# ST-Link-V2_2-Mini.net
KiCad netlist of a schematic drawn in Altium Designer
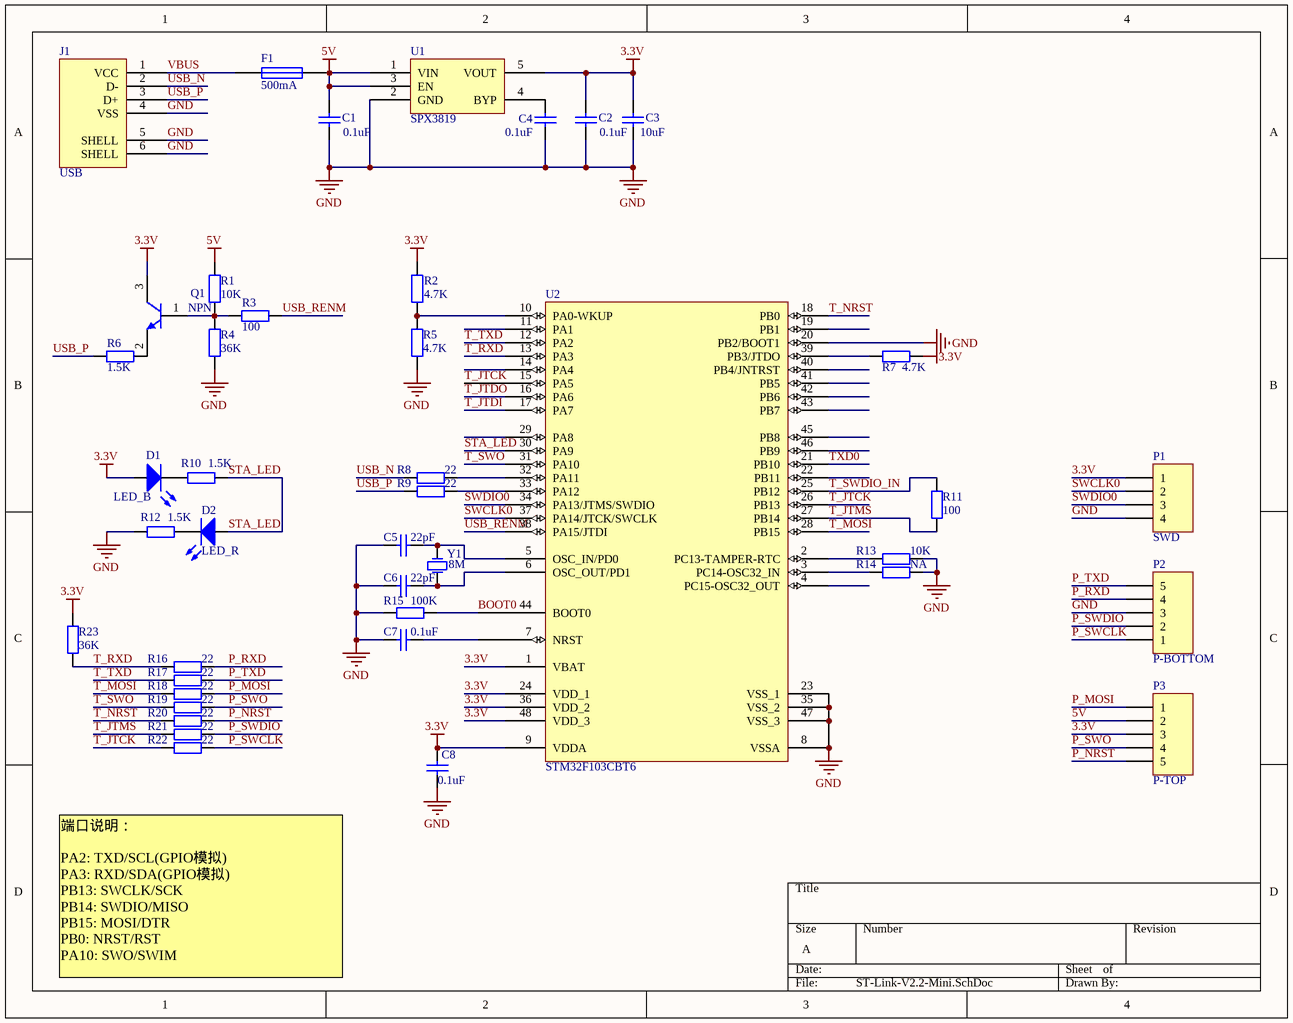
[diagram p0: ST-Link-V2.2-Mini.SchDoc]

(export (version "E")
  (design (tool "Eeschema 10.0.6"))
  (components
    (comp (ref "C1")
      (value "0.1uF")
      (footprint "C-0603")
      (description "Capacitor")
      (fields (field (name "Comment") "Cap") (field (name "PUBLISHER") "Altium Limited"))
      (libsource (lib "Miscellaneous Devices") (part "Cap"))
    )
    (comp (ref "C2")
      (value "0.1uF")
      (footprint "C-0603")
      (description "Capacitor")
      (fields (field (name "Comment") "Cap") (field (name "PUBLISHER") "Altium Limited"))
      (libsource (lib "Miscellaneous Devices") (part "Cap"))
    )
    (comp (ref "C3")
      (value "10uF")
      (footprint "C-0603")
      (description "Capacitor")
      (fields (field (name "Comment") "Cap") (field (name "PUBLISHER") "Altium Limited"))
      (libsource (lib "Miscellaneous Devices") (part "Cap"))
    )
    (comp (ref "C4")
      (value "0.1uF")
      (footprint "C-0603")
      (description "Capacitor")
      (fields (field (name "Comment") "Cap") (field (name "PUBLISHER") "Altium Limited"))
      (libsource (lib "Miscellaneous Devices") (part "Cap"))
    )
    (comp (ref "C5")
      (value "22pF")
      (footprint "C-0603")
      (fields (field (name "Comment") "Cap"))
      (libsource (lib "WK_PCB") (part "Cap"))
    )
    (comp (ref "C6")
      (value "22pF")
      (footprint "C-0603")
      (fields (field (name "Comment") "Cap"))
      (libsource (lib "WK_PCB") (part "Cap"))
    )
    (comp (ref "C7")
      (value "0.1uF")
      (footprint "C-0603")
      (fields (field (name "Comment") "Cap"))
      (libsource (lib "WK_PCB") (part "Cap"))
    )
    (comp (ref "C8")
      (value "0.1uF")
      (footprint "C-0603")
      (description "Capacitor")
      (fields (field (name "Comment") "Cap") (field (name "PUBLISHER") "Altium Limited"))
      (libsource (lib "Miscellaneous Devices") (part "Cap"))
    )
    (comp (ref "D1")
      (value "LED_B")
      (footprint "SMT_LED_0603")
      (description "Typical RED, GREEN, YELLOW, AMBER GaAs LED")
      (fields (field (name "PUBLISHER") "Altium Limited"))
      (libsource (lib "ST-Link-V2.2") (part "LED2"))
    )
    (comp (ref "D2")
      (value "LED_R")
      (footprint "SMT_LED_0603")
      (description "Typical RED, GREEN, YELLOW, AMBER GaAs LED")
      (fields (field (name "PUBLISHER") "Altium Limited"))
      (libsource (lib "ST-Link-V2.2") (part "LED2"))
    )
    (comp (ref "F1")
      (value "500mA")
      (footprint "0805-1")
      (description "保险丝")
      (fields (field (name "Comment") "Fuse1"))
      (libsource (lib "ST-Link-V2.2") (part "Fuse1"))
    )
    (comp (ref "J1")
      (value "USB")
      (footprint "USB-B")
      (description "USB接口")
      (libsource (lib "HDR_Fszhang") (part "USB"))
    )
    (comp (ref "P1")
      (value "SWD")
      (footprint "SIP4-1.27")
      (description "Header, 4-Pin")
      (fields (field (name "PUBLISHER") "Altium Limited"))
      (libsource (lib "Miscellaneous Connectors") (part "Header 4"))
    )
    (comp (ref "P2")
      (value "P-BOTTOM")
      (footprint "HEADER_5")
      (description "Header, 5-Pin")
      (fields (field (name "PUBLISHER") "Altium Limited"))
      (libsource (lib "Miscellaneous Connectors") (part "Header 5"))
    )
    (comp (ref "P3")
      (value "P-TOP")
      (footprint "HEADER_5")
      (description "Header, 5-Pin")
      (fields (field (name "PUBLISHER") "Altium Limited"))
      (libsource (lib "") (part "Header 5_1"))
    )
    (comp (ref "Q1")
      (value "NPN")
      (footprint "SOT23-3")
      (description "贴片三极管")
      (fields (field (name "PUBLISHER") "Altium Limited"))
      (libsource (lib "Fszhang") (part "NPN1"))
    )
    (comp (ref "R1")
      (value "10K")
      (footprint "0603-1")
      (description "贴片电阻")
      (fields (field (name "Comment") "Res1") (field (name "PUBLISHER") "Altium Limited"))
      (libsource (lib "Fszhang") (part "Res1"))
    )
    (comp (ref "R2")
      (value "4.7K")
      (footprint "0603-1")
      (description "Resistor")
      (fields (field (name "Comment") "Res2") (field (name "PUBLISHER") "Altium Limited"))
      (libsource (lib "") (part "Res2_1"))
    )
    (comp (ref "R3")
      (value "100")
      (footprint "0603-1")
      (description "贴片电阻")
      (fields (field (name "Comment") "Res1") (field (name "PUBLISHER") "Altium Limited"))
      (libsource (lib "") (part "Res1_2"))
    )
    (comp (ref "R4")
      (value "36K")
      (footprint "0603-1")
      (description "贴片电阻")
      (fields (field (name "Comment") "Res1") (field (name "PUBLISHER") "Altium Limited"))
      (libsource (lib "Fszhang") (part "Res1"))
    )
    (comp (ref "R5")
      (value "4.7K")
      (footprint "0603-1")
      (description "Resistor")
      (fields (field (name "Comment") "Res2") (field (name "PUBLISHER") "Altium Limited"))
      (libsource (lib "") (part "Res2_1"))
    )
    (comp (ref "R6")
      (value "1.5K")
      (footprint "0603-1")
      (description "贴片电阻")
      (fields (field (name "Comment") "Res1") (field (name "PUBLISHER") "Altium Limited"))
      (libsource (lib "") (part "Res1_1"))
    )
    (comp (ref "R7")
      (value "4.7K")
      (footprint "0603-1")
      (description "Resistor")
      (fields (field (name "Comment") "Res2") (field (name "PUBLISHER") "Altium Limited"))
      (libsource (lib "Miscellaneous Devices") (part "Res2"))
    )
    (comp (ref "R8")
      (value "22")
      (footprint "0603-1")
      (description "Resistor")
      (fields (field (name "Comment") "Res2") (field (name "PUBLISHER") "Altium Limited"))
      (libsource (lib "Miscellaneous Devices") (part "Res2"))
    )
    (comp (ref "R9")
      (value "22")
      (footprint "0603-1")
      (description "Resistor")
      (fields (field (name "Comment") "Res2") (field (name "PUBLISHER") "Altium Limited"))
      (libsource (lib "Miscellaneous Devices") (part "Res2"))
    )
    (comp (ref "R10")
      (value "1.5K")
      (footprint "0603-1")
      (description "Resistor")
      (fields (field (name "Comment") "Res2") (field (name "PUBLISHER") "Altium Limited"))
      (libsource (lib "Miscellaneous Devices") (part "Res2"))
    )
    (comp (ref "R11")
      (value "100")
      (footprint "0603-1")
      (description "Resistor")
      (fields (field (name "Comment") "Res2") (field (name "PUBLISHER") "Altium Limited"))
      (libsource (lib "") (part "Res2_1"))
    )
    (comp (ref "R12")
      (value "1.5K")
      (footprint "0603-1")
      (description "Resistor")
      (fields (field (name "Comment") "Res2") (field (name "PUBLISHER") "Altium Limited"))
      (libsource (lib "") (part "Res2_1"))
    )
    (comp (ref "R13")
      (value "10K")
      (footprint "0603-1")
      (description "贴片电阻")
      (fields (field (name "Comment") "Res1") (field (name "PUBLISHER") "Altium Limited"))
      (libsource (lib "") (part "Res1_2"))
    )
    (comp (ref "R14")
      (value "NA")
      (footprint "0603-1")
      (description "贴片电阻")
      (fields (field (name "Comment") "Res1") (field (name "PUBLISHER") "Altium Limited"))
      (libsource (lib "") (part "Res1_2"))
    )
    (comp (ref "R15")
      (value "100K")
      (footprint "0603-1")
      (description "Resistor")
      (fields (field (name "Comment") "Res2") (field (name "PUBLISHER") "Altium Limited"))
      (libsource (lib "Miscellaneous Devices") (part "Res2"))
    )
    (comp (ref "R16")
      (value "22")
      (footprint "0603-1")
      (description "Resistor")
      (fields (field (name "Comment") "Res2") (field (name "PUBLISHER") "Altium Limited"))
      (libsource (lib "Miscellaneous Devices") (part "Res2"))
    )
    (comp (ref "R17")
      (value "22")
      (footprint "0603-1")
      (description "Resistor")
      (fields (field (name "Comment") "Res2") (field (name "PUBLISHER") "Altium Limited"))
      (libsource (lib "Miscellaneous Devices") (part "Res2"))
    )
    (comp (ref "R18")
      (value "22")
      (footprint "0603-1")
      (description "Resistor")
      (fields (field (name "Comment") "Res2") (field (name "PUBLISHER") "Altium Limited"))
      (libsource (lib "Miscellaneous Devices") (part "Res2"))
    )
    (comp (ref "R19")
      (value "22")
      (footprint "0603-1")
      (description "Resistor")
      (fields (field (name "Comment") "Res2") (field (name "PUBLISHER") "Altium Limited"))
      (libsource (lib "Miscellaneous Devices") (part "Res2"))
    )
    (comp (ref "R20")
      (value "22")
      (footprint "0603-1")
      (description "Resistor")
      (fields (field (name "Comment") "Res2") (field (name "PUBLISHER") "Altium Limited"))
      (libsource (lib "Miscellaneous Devices") (part "Res2"))
    )
    (comp (ref "R21")
      (value "22")
      (footprint "0603-1")
      (description "Resistor")
      (fields (field (name "Comment") "Res2") (field (name "PUBLISHER") "Altium Limited"))
      (libsource (lib "Miscellaneous Devices") (part "Res2"))
    )
    (comp (ref "R22")
      (value "22")
      (footprint "0603-1")
      (description "Resistor")
      (fields (field (name "Comment") "Res2") (field (name "PUBLISHER") "Altium Limited"))
      (libsource (lib "Miscellaneous Devices") (part "Res2"))
    )
    (comp (ref "R23")
      (value "36K")
      (footprint "0603-1")
      (description "贴片电阻")
      (fields (field (name "Comment") "Res1") (field (name "PUBLISHER") "Altium Limited"))
      (libsource (lib "Fszhang") (part "Res1"))
    )
    (comp (ref "U1") (value "SPX3819") (footprint "SOT23-5") (libsource (lib "Schlib1") (part "SPX3819")))
    (comp (ref "U2")
      (value "STM32F103CBT6")
      (footprint "LQFP48_N")
      (description "STM32 ARM-based 32-bit MCU with 64 Kbytes Flash, 48-pin LQFP, Industrial Temperature")
      (fields (field (name "PUBLISHER") "Altium Limited"))
      (libsource (lib "ST Microcontroller 32-Bit STM32") (part "STM32F103C8T6"))
    )
    (comp (ref "Y1")
      (value "8M")
      (footprint "XAL5032 2-Leads")
      (description "Crystal Oscillator")
      (fields
        (field (name "MANUFACTURER") "Generic Components")
        (field (name "PUBLISHER") "Altium Hobart Technology Centre")
      )
      (libsource (lib "*") (part "XTAL"))
    )
  )
  (nets
    (net (code "1") (name "/BOOT0") (class "Default")
      (node (ref "R15") (pin "2") (pinfunction "2_2") (pintype "passive"))
      (node (ref "U2") (pin "44") (pinfunction "BOOT0_44") (pintype "passive"))
    )
    (net (code "2") (name "/P_MOSI") (class "Default")
      (node (ref "P3") (pin "1") (pinfunction "1_1") (pintype "passive"))
      (node (ref "R18") (pin "2") (pinfunction "2_2") (pintype "passive"))
    )
    (net (code "3") (name "/P_NRST") (class "Default")
      (node (ref "P3") (pin "5") (pinfunction "5_5") (pintype "passive"))
      (node (ref "R20") (pin "2") (pinfunction "2_2") (pintype "passive"))
    )
    (net (code "4") (name "/P_RXD") (class "Default")
      (node (ref "P2") (pin "4") (pinfunction "4_4") (pintype "passive"))
      (node (ref "R16") (pin "2") (pinfunction "2_2") (pintype "passive"))
    )
    (net (code "5") (name "/P_SWCLK") (class "Default")
      (node (ref "P2") (pin "1") (pinfunction "1_1") (pintype "passive"))
      (node (ref "R22") (pin "2") (pinfunction "2_2") (pintype "passive"))
    )
    (net (code "6") (name "/P_SWDIO") (class "Default")
      (node (ref "P2") (pin "2") (pinfunction "2_2") (pintype "passive"))
      (node (ref "R21") (pin "2") (pinfunction "2_2") (pintype "passive"))
    )
    (net (code "7") (name "/P_SWO") (class "Default")
      (node (ref "P3") (pin "4") (pinfunction "4_4") (pintype "passive"))
      (node (ref "R19") (pin "2") (pinfunction "2_2") (pintype "passive"))
    )
    (net (code "8") (name "/P_TXD") (class "Default")
      (node (ref "P2") (pin "5") (pinfunction "5_5") (pintype "passive"))
      (node (ref "R17") (pin "2") (pinfunction "2_2") (pintype "passive"))
    )
    (net (code "9") (name "/STA_LED") (class "Default")
      (node (ref "D2") (pin "1") (pinfunction "A_1") (pintype "passive"))
      (node (ref "R10") (pin "2") (pinfunction "2_2") (pintype "passive"))
      (node (ref "U2") (pin "30") (pinfunction "PA9_30") (pintype "bidirectional"))
    )
    (net (code "10") (name "/SWCLK0") (class "Default")
      (node (ref "P1") (pin "2") (pinfunction "2_2") (pintype "passive"))
      (node (ref "U2") (pin "37") (pinfunction "PA14/JTCK/SWCLK_37") (pintype "bidirectional"))
    )
    (net (code "11") (name "/SWDIO0") (class "Default")
      (node (ref "P1") (pin "3") (pinfunction "3_3") (pintype "passive"))
      (node (ref "U2") (pin "34") (pinfunction "PA13/JTMS/SWDIO_34") (pintype "bidirectional"))
    )
    (net (code "12") (name "/TXD0") (class "Default")
      (node (ref "U2") (pin "21") (pinfunction "PB10_21") (pintype "bidirectional"))
    )
    (net (code "13") (name "/T_JTCK") (class "Default")
      (node (ref "R22") (pin "1") (pinfunction "1_1") (pintype "passive"))
      (node (ref "U2") (pin "15") (pinfunction "PA5_15") (pintype "bidirectional"))
      (node (ref "U2") (pin "26") (pinfunction "PB13_26") (pintype "bidirectional"))
    )
    (net (code "14") (name "/T_JTDI") (class "Default")
      (node (ref "U2") (pin "17") (pinfunction "PA7_17") (pintype "bidirectional"))
    )
    (net (code "15") (name "/T_JTDO") (class "Default")
      (node (ref "U2") (pin "16") (pinfunction "PA6_16") (pintype "bidirectional"))
    )
    (net (code "16") (name "/T_JTMS") (class "Default")
      (node (ref "R11") (pin "1") (pinfunction "1_1") (pintype "passive"))
      (node (ref "R21") (pin "1") (pinfunction "1_1") (pintype "passive"))
      (node (ref "U2") (pin "27") (pinfunction "PB14_27") (pintype "bidirectional"))
    )
    (net (code "17") (name "/T_MOSI") (class "Default")
      (node (ref "R18") (pin "1") (pinfunction "1_1") (pintype "passive"))
      (node (ref "U2") (pin "28") (pinfunction "PB15_28") (pintype "bidirectional"))
    )
    (net (code "18") (name "/T_NRST") (class "Default")
      (node (ref "R20") (pin "1") (pinfunction "1_1") (pintype "passive"))
      (node (ref "U2") (pin "18") (pinfunction "PB0_18") (pintype "bidirectional"))
    )
    (net (code "19") (name "/T_RXD") (class "Default")
      (node (ref "R16") (pin "1") (pinfunction "1_1") (pintype "passive"))
      (node (ref "R23") (pin "2") (pinfunction "2_2") (pintype "passive"))
      (node (ref "U2") (pin "13") (pinfunction "PA3_13") (pintype "bidirectional"))
    )
    (net (code "20") (name "/T_SWDIO_IN") (class "Default")
      (node (ref "R11") (pin "2") (pinfunction "2_2") (pintype "passive"))
      (node (ref "U2") (pin "25") (pinfunction "PB12_25") (pintype "bidirectional"))
    )
    (net (code "21") (name "/T_SWO") (class "Default")
      (node (ref "R19") (pin "1") (pinfunction "1_1") (pintype "passive"))
      (node (ref "U2") (pin "31") (pinfunction "PA10_31") (pintype "bidirectional"))
    )
    (net (code "22") (name "/T_TXD") (class "Default")
      (node (ref "R17") (pin "1") (pinfunction "1_1") (pintype "passive"))
      (node (ref "U2") (pin "12") (pinfunction "PA2_12") (pintype "bidirectional"))
    )
    (net (code "23") (name "/USB_N") (class "Default")
      (node (ref "J1") (pin "2") (pinfunction "D-_2") (pintype "passive"))
      (node (ref "R8") (pin "1") (pinfunction "1_1") (pintype "passive"))
    )
    (net (code "24") (name "/USB_P") (class "Default")
      (node (ref "J1") (pin "3") (pinfunction "D+_3") (pintype "passive"))
      (node (ref "R6") (pin "2") (pinfunction "2_2") (pintype "passive"))
      (node (ref "R9") (pin "1") (pinfunction "1_1") (pintype "passive"))
    )
    (net (code "25") (name "/USB_RENM") (class "Default")
      (node (ref "R3") (pin "2") (pinfunction "2_2") (pintype "passive"))
      (node (ref "U2") (pin "38") (pinfunction "PA15/JTDI_38") (pintype "bidirectional"))
    )
    (net (code "26") (name "/VBUS") (class "Default")
      (node (ref "F1") (pin "1") (pinfunction "1_1") (pintype "passive"))
      (node (ref "J1") (pin "1") (pinfunction "VCC_1") (pintype "passive"))
    )
    (net (code "27") (name "3.3V") (class "Default")
      (node (ref "C2") (pin "2") (pinfunction "2_2") (pintype "passive"))
      (node (ref "C3") (pin "2") (pinfunction "2_2") (pintype "passive"))
      (node (ref "C8") (pin "2") (pinfunction "2_2") (pintype "passive"))
      (node (ref "D1") (pin "1") (pinfunction "A_1") (pintype "passive"))
      (node (ref "P1") (pin "1") (pinfunction "1_1") (pintype "passive"))
      (node (ref "P3") (pin "3") (pinfunction "3_3") (pintype "passive"))
      (node (ref "Q1") (pin "3") (pinfunction "C_3") (pintype "passive"))
      (node (ref "R2") (pin "2") (pinfunction "2_2") (pintype "passive"))
      (node (ref "R23") (pin "1") (pinfunction "1_1") (pintype "passive"))
      (node (ref "R7") (pin "2") (pinfunction "2_2") (pintype "passive"))
      (node (ref "U1") (pin "5") (pinfunction "VOUT_5") (pintype "passive"))
      (node (ref "U2") (pin "1") (pinfunction "VBAT_1") (pintype "power_in"))
      (node (ref "U2") (pin "24") (pinfunction "VDD_1_24") (pintype "power_in"))
      (node (ref "U2") (pin "36") (pinfunction "VDD_2_36") (pintype "power_in"))
      (node (ref "U2") (pin "48") (pinfunction "VDD_3_48") (pintype "power_in"))
      (node (ref "U2") (pin "9") (pinfunction "VDDA_9") (pintype "power_in"))
    )
    (net (code "28") (name "5V") (class "Default")
      (node (ref "C1") (pin "2") (pinfunction "2_2") (pintype "passive"))
      (node (ref "F1") (pin "2") (pinfunction "2_2") (pintype "passive"))
      (node (ref "P3") (pin "2") (pinfunction "2_2") (pintype "passive"))
      (node (ref "R1") (pin "1") (pinfunction "1_1") (pintype "passive"))
      (node (ref "U1") (pin "1") (pinfunction "VIN_1") (pintype "passive"))
      (node (ref "U1") (pin "3") (pinfunction "EN_3") (pintype "passive"))
    )
    (net (code "29") (name "GND") (class "Default")
      (node (ref "C1") (pin "1") (pinfunction "1_1") (pintype "passive"))
      (node (ref "C2") (pin "1") (pinfunction "1_1") (pintype "passive"))
      (node (ref "C3") (pin "1") (pinfunction "1_1") (pintype "passive"))
      (node (ref "C4") (pin "1") (pinfunction "1_1") (pintype "passive"))
      (node (ref "C5") (pin "1") (pinfunction "1_1") (pintype "passive"))
      (node (ref "C6") (pin "1") (pinfunction "1_1") (pintype "passive"))
      (node (ref "C7") (pin "1") (pinfunction "1_1") (pintype "passive"))
      (node (ref "C8") (pin "1") (pinfunction "1_1") (pintype "passive"))
      (node (ref "J1") (pin "4") (pinfunction "VSS_4") (pintype "passive"))
      (node (ref "J1") (pin "5") (pinfunction "SHELL_5") (pintype "passive"))
      (node (ref "J1") (pin "6") (pinfunction "SHELL_6") (pintype "passive"))
      (node (ref "P1") (pin "4") (pinfunction "4_4") (pintype "passive"))
      (node (ref "P2") (pin "3") (pinfunction "3_3") (pintype "passive"))
      (node (ref "R12") (pin "1") (pinfunction "1_1") (pintype "passive"))
      (node (ref "R13") (pin "2") (pinfunction "2_2") (pintype "passive"))
      (node (ref "R14") (pin "2") (pinfunction "2_2") (pintype "passive"))
      (node (ref "R15") (pin "1") (pinfunction "1_1") (pintype "passive"))
      (node (ref "R4") (pin "2") (pinfunction "2_2") (pintype "passive"))
      (node (ref "R5") (pin "1") (pinfunction "1_1") (pintype "passive"))
      (node (ref "U1") (pin "2") (pinfunction "GND_2") (pintype "passive"))
      (node (ref "U2") (pin "20") (pinfunction "PB2/BOOT1_20") (pintype "bidirectional"))
      (node (ref "U2") (pin "23") (pinfunction "VSS_1_23") (pintype "power_in"))
      (node (ref "U2") (pin "35") (pinfunction "VSS_2_35") (pintype "power_in"))
      (node (ref "U2") (pin "47") (pinfunction "VSS_3_47") (pintype "power_in"))
      (node (ref "U2") (pin "8") (pinfunction "VSSA_8") (pintype "power_in"))
    )
    (net (code "30") (name "Net-(D1-K)") (class "Default")
      (node (ref "D1") (pin "2") (pinfunction "K_2") (pintype "passive"))
      (node (ref "R10") (pin "1") (pinfunction "1_1") (pintype "passive"))
    )
    (net (code "31") (name "Net-(D2-K)") (class "Default")
      (node (ref "D2") (pin "2") (pinfunction "K_2") (pintype "passive"))
      (node (ref "R12") (pin "2") (pinfunction "2_2") (pintype "passive"))
    )
    (net (code "32") (name "Net-(Q1-B)") (class "Default")
      (node (ref "Q1") (pin "1") (pinfunction "B_1") (pintype "passive"))
      (node (ref "R1") (pin "2") (pinfunction "2_2") (pintype "passive"))
      (node (ref "R3") (pin "1") (pinfunction "1_1") (pintype "passive"))
      (node (ref "R4") (pin "1") (pinfunction "1_1") (pintype "passive"))
    )
    (net (code "33") (name "Net-(Q1-E)") (class "Default")
      (node (ref "Q1") (pin "2") (pinfunction "E_2") (pintype "passive"))
      (node (ref "R6") (pin "1") (pinfunction "1_1") (pintype "passive"))
    )
    (net (code "34") (name "Net-(U1-BYP)") (class "Default")
      (node (ref "C4") (pin "2") (pinfunction "2_2") (pintype "passive"))
      (node (ref "U1") (pin "4") (pinfunction "BYP_4") (pintype "passive"))
    )
    (net (code "35") (name "Net-(U2-NRST)") (class "Default")
      (node (ref "C7") (pin "2") (pinfunction "2_2") (pintype "passive"))
      (node (ref "U2") (pin "7") (pinfunction "NRST_7") (pintype "bidirectional"))
    )
    (net (code "36") (name "Net-(U2-OSC_IN{slash}PD0)") (class "Default")
      (node (ref "C5") (pin "2") (pinfunction "2_2") (pintype "passive"))
      (node (ref "U2") (pin "5") (pinfunction "OSC_IN/PD0_5") (pintype "passive"))
      (node (ref "Y1") (pin "1") (pinfunction "OSC1_1") (pintype "passive"))
    )
    (net (code "37") (name "Net-(U2-OSC_OUT{slash}PD1)") (class "Default")
      (node (ref "C6") (pin "2") (pinfunction "2_2") (pintype "passive"))
      (node (ref "U2") (pin "6") (pinfunction "OSC_OUT/PD1_6") (pintype "passive"))
      (node (ref "Y1") (pin "2") (pinfunction "OSC2_2") (pintype "passive"))
    )
    (net (code "38") (name "Net-(U2-PA0-WKUP)") (class "Default")
      (node (ref "R2") (pin "1") (pinfunction "1_1") (pintype "passive"))
      (node (ref "R5") (pin "2") (pinfunction "2_2") (pintype "passive"))
      (node (ref "U2") (pin "10") (pinfunction "PA0-WKUP_10") (pintype "bidirectional"))
    )
    (net (code "39") (name "Net-(U2-PA11)") (class "Default")
      (node (ref "R8") (pin "2") (pinfunction "2_2") (pintype "passive"))
      (node (ref "U2") (pin "32") (pinfunction "PA11_32") (pintype "bidirectional"))
    )
    (net (code "40") (name "Net-(U2-PA12)") (class "Default")
      (node (ref "R9") (pin "2") (pinfunction "2_2") (pintype "passive"))
      (node (ref "U2") (pin "33") (pinfunction "PA12_33") (pintype "bidirectional"))
    )
    (net (code "41") (name "Net-(U2-PB3{slash}JTDO)") (class "Default")
      (node (ref "R7") (pin "1") (pinfunction "1_1") (pintype "passive"))
      (node (ref "U2") (pin "39") (pinfunction "PB3/JTDO_39") (pintype "bidirectional"))
    )
    (net (code "42") (name "Net-(U2-PC13-TAMPER-RTC)") (class "Default")
      (node (ref "R13") (pin "1") (pinfunction "1_1") (pintype "passive"))
      (node (ref "U2") (pin "2") (pinfunction "PC13-TAMPER-RTC_2") (pintype "bidirectional"))
    )
    (net (code "43") (name "Net-(U2-PC14-OSC32_IN)") (class "Default")
      (node (ref "R14") (pin "1") (pinfunction "1_1") (pintype "passive"))
      (node (ref "U2") (pin "3") (pinfunction "PC14-OSC32_IN_3") (pintype "bidirectional"))
    )
    (net (code "44") (name "unconnected-(U2-PA1-Pad11)") (class "Default")
      (node (ref "U2") (pin "11") (pinfunction "PA1_11") (pintype "bidirectional"))
    )
    (net (code "45") (name "unconnected-(U2-PA4-Pad14)") (class "Default")
      (node (ref "U2") (pin "14") (pinfunction "PA4_14") (pintype "bidirectional"))
    )
    (net (code "46") (name "unconnected-(U2-PA8-Pad29)") (class "Default")
      (node (ref "U2") (pin "29") (pinfunction "PA8_29") (pintype "bidirectional"))
    )
    (net (code "47") (name "unconnected-(U2-PB1-Pad19)") (class "Default")
      (node (ref "U2") (pin "19") (pinfunction "PB1_19") (pintype "bidirectional"))
    )
    (net (code "48") (name "unconnected-(U2-PB4{slash}JNTRST-Pad40)") (class "Default")
      (node (ref "U2") (pin "40") (pinfunction "PB4/JNTRST_40") (pintype "bidirectional"))
    )
    (net (code "49") (name "unconnected-(U2-PB5-Pad41)") (class "Default")
      (node (ref "U2") (pin "41") (pinfunction "PB5_41") (pintype "bidirectional"))
    )
    (net (code "50") (name "unconnected-(U2-PB6-Pad42)") (class "Default")
      (node (ref "U2") (pin "42") (pinfunction "PB6_42") (pintype "bidirectional"))
    )
    (net (code "51") (name "unconnected-(U2-PB7-Pad43)") (class "Default")
      (node (ref "U2") (pin "43") (pinfunction "PB7_43") (pintype "bidirectional"))
    )
    (net (code "52") (name "unconnected-(U2-PB8-Pad45)") (class "Default")
      (node (ref "U2") (pin "45") (pinfunction "PB8_45") (pintype "bidirectional"))
    )
    (net (code "53") (name "unconnected-(U2-PB9-Pad46)") (class "Default")
      (node (ref "U2") (pin "46") (pinfunction "PB9_46") (pintype "bidirectional"))
    )
    (net (code "54") (name "unconnected-(U2-PB11-Pad22)") (class "Default")
      (node (ref "U2") (pin "22") (pinfunction "PB11_22") (pintype "bidirectional"))
    )
    (net (code "55") (name "unconnected-(U2-PC15-OSC32_OUT-Pad4)") (class "Default")
      (node (ref "U2") (pin "4") (pinfunction "PC15-OSC32_OUT_4") (pintype "bidirectional"))
    )
  )
)
